# Adafruit_HX711_ADC_Breakout.net
KiCad netlist of a schematic drawn in EAGLE
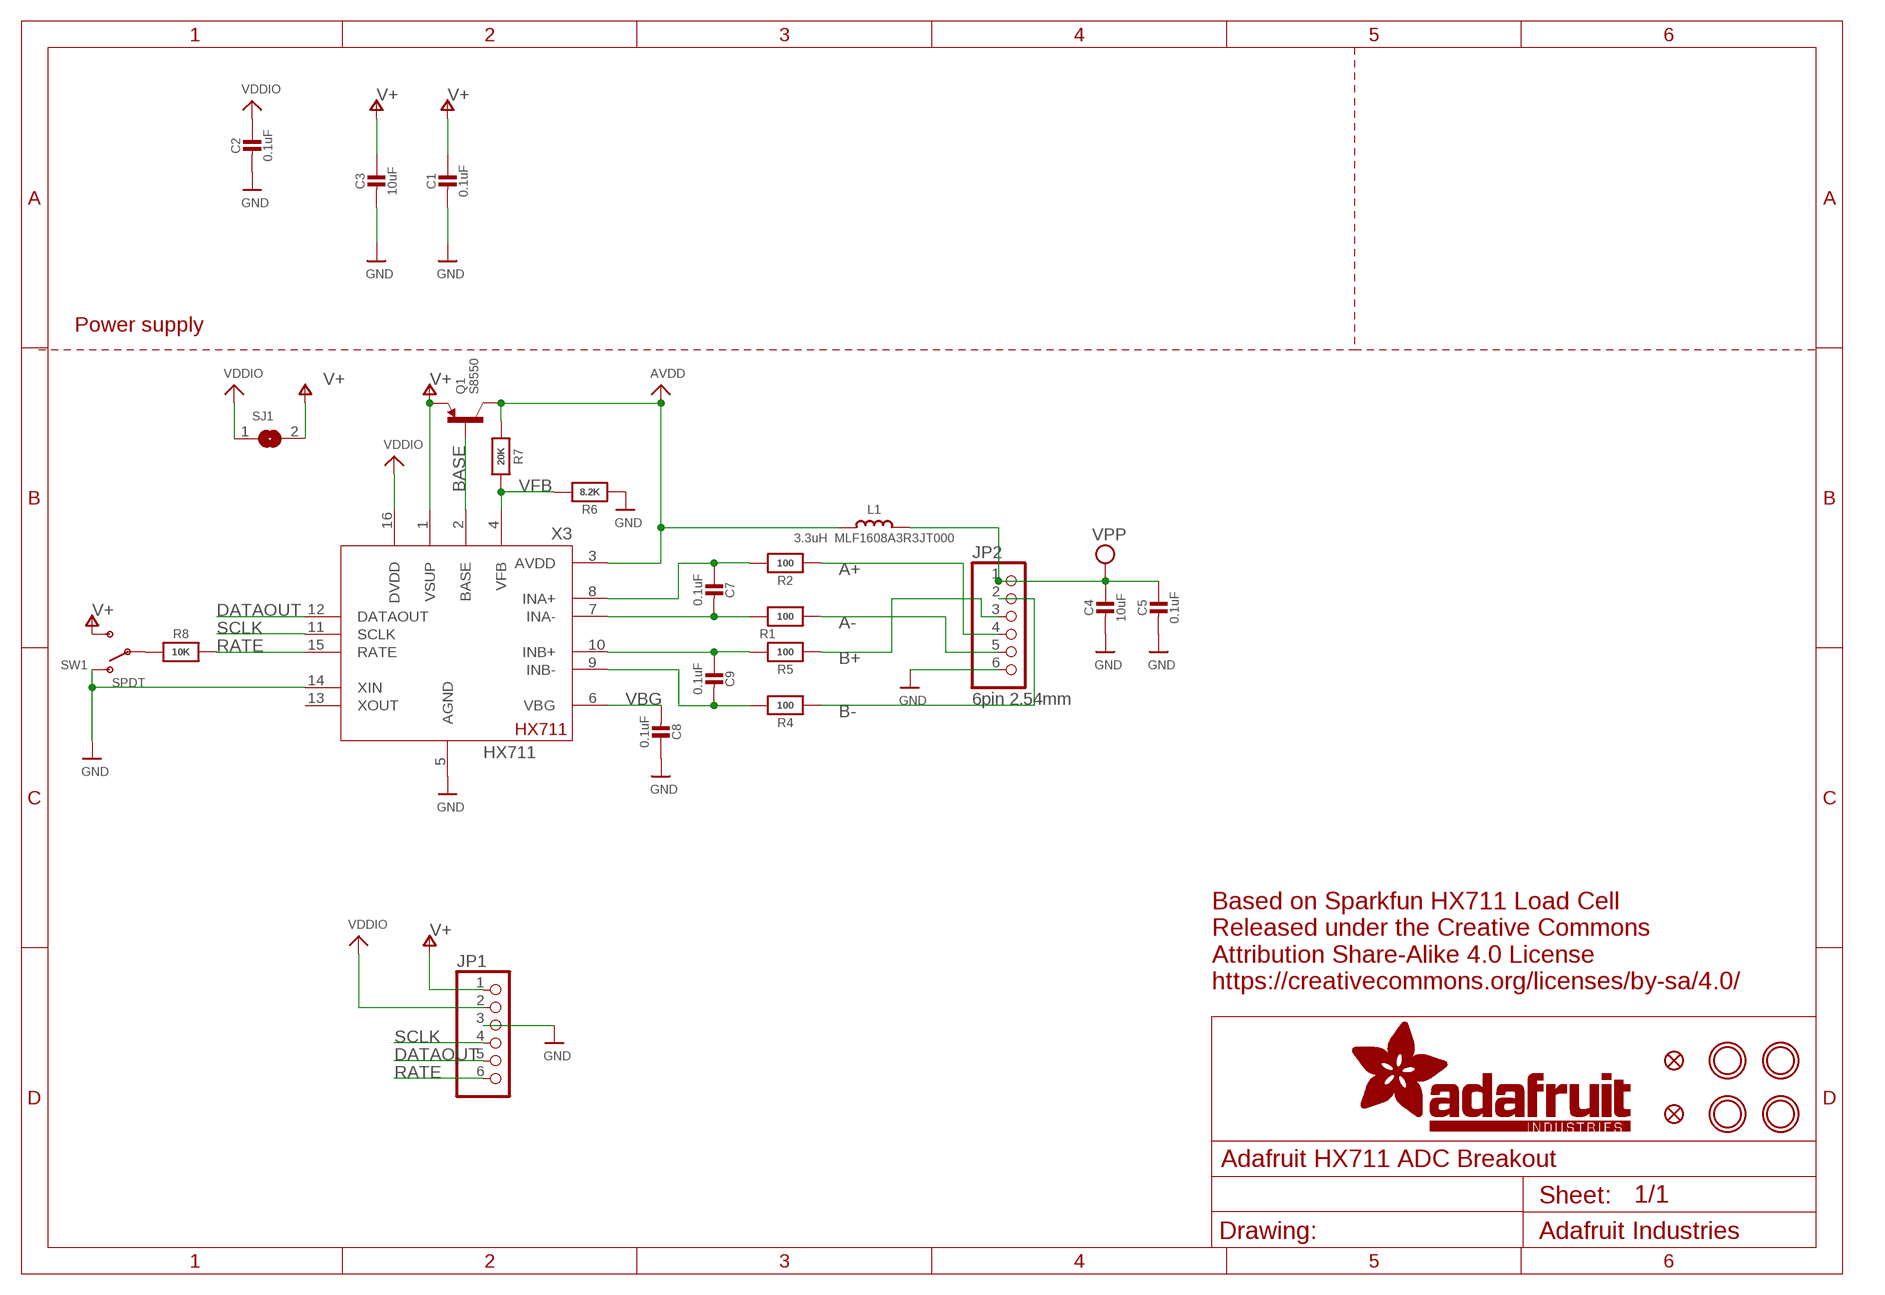
[diagram p0: schematic, sheet 1]

(export (version "E")
  (design (tool "Eeschema 10.0.6"))
  (components
    (comp (ref "C1")
      (value "0.1uF")
      (footprint "eagle-import:0603-NO")
      (libsource (lib "eagle-import") (part "CAP_CERAMIC0603_NO"))
    )
    (comp (ref "C2")
      (value "0.1uF")
      (footprint "eagle-import:0603-NO")
      (libsource (lib "eagle-import") (part "CAP_CERAMIC0603_NO"))
    )
    (comp (ref "C3")
      (value "10uF")
      (footprint "eagle-import:0805-NO")
      (libsource (lib "eagle-import") (part "CAP_CERAMIC0805-NOOUTLINE"))
    )
    (comp (ref "C4")
      (value "10uF")
      (footprint "eagle-import:0805-NO")
      (libsource (lib "eagle-import") (part "CAP_CERAMIC0805-NOOUTLINE"))
    )
    (comp (ref "C5")
      (value "0.1uF")
      (footprint "eagle-import:0603-NO")
      (libsource (lib "eagle-import") (part "CAP_CERAMIC0603_NO"))
    )
    (comp (ref "C7")
      (value "0.1uF")
      (footprint "eagle-import:0603-NO")
      (libsource (lib "eagle-import") (part "CAP_CERAMIC0603_NO"))
    )
    (comp (ref "C8")
      (value "0.1uF")
      (footprint "eagle-import:0603-NO")
      (libsource (lib "eagle-import") (part "CAP_CERAMIC0603_NO"))
    )
    (comp (ref "C9")
      (value "0.1uF")
      (footprint "eagle-import:0603-NO")
      (libsource (lib "eagle-import") (part "CAP_CERAMIC0603_NO"))
    )
    (comp (ref "FID3")
      (value "FIDUCIAL_0.5MM")
      (footprint "eagle-import:FIDUCIAL_0.5MM")
      (libsource (lib "eagle-import") (part "FIDUCIAL_0.5MM"))
    )
    (comp (ref "FID4")
      (value "FIDUCIAL_0.5MM")
      (footprint "eagle-import:FIDUCIAL_0.5MM")
      (libsource (lib "eagle-import") (part "FIDUCIAL_0.5MM"))
    )
    (comp (ref "JP1")
      (value "HEADER-1X670MIL")
      (footprint "eagle-import:1X06_ROUND_70")
      (libsource (lib "eagle-import") (part "HEADER-1X670MIL"))
    )
    (comp (ref "JP2")
      (value "6pin 2.54mm")
      (footprint "eagle-import:1X06_2.54MMTERMINAL")
      (libsource (lib "eagle-import") (part "HEADER-1X6_2.54MMTERM"))
    )
    (comp (ref "L1")
      (value "3.3uH MLF1608A3R3JT000")
      (footprint "eagle-import:0603-NO")
      (libsource (lib "eagle-import") (part "INDUCTOR0603_NO"))
    )
    (comp (ref "Q1")
      (value "S8550")
      (footprint "eagle-import:SOT23-WIDE")
      (libsource (lib "eagle-import") (part "TRANSISTOR_PNPWIDE"))
    )
    (comp (ref "R1")
      (value "100")
      (footprint "eagle-import:0603-NO")
      (libsource (lib "eagle-import") (part "RESISTOR_0603_NOOUT"))
    )
    (comp (ref "R2")
      (value "100")
      (footprint "eagle-import:0603-NO")
      (libsource (lib "eagle-import") (part "RESISTOR_0603_NOOUT"))
    )
    (comp (ref "R4")
      (value "100")
      (footprint "eagle-import:0603-NO")
      (libsource (lib "eagle-import") (part "RESISTOR_0603_NOOUT"))
    )
    (comp (ref "R5")
      (value "100")
      (footprint "eagle-import:0603-NO")
      (libsource (lib "eagle-import") (part "RESISTOR_0603_NOOUT"))
    )
    (comp (ref "R6")
      (value "8.2K")
      (footprint "eagle-import:0603-NO")
      (libsource (lib "eagle-import") (part "RESISTOR_0603_NOOUT"))
    )
    (comp (ref "R7")
      (value "20K")
      (footprint "eagle-import:0603-NO")
      (libsource (lib "eagle-import") (part "RESISTOR_0603_NOOUT"))
    )
    (comp (ref "R8")
      (value "10K")
      (footprint "eagle-import:0603-NO")
      (libsource (lib "eagle-import") (part "RESISTOR_0603_NOOUT"))
    )
    (comp (ref "SJ1")
      (value "SOLDERJUMPER")
      (footprint "eagle-import:SOLDERJUMPER_ARROW_NOPASTE")
      (libsource (lib "eagle-import") (part "SOLDERJUMPER"))
    )
    (comp (ref "SW1")
      (value "SPDT")
      (footprint "eagle-import:SPDT_SMT_SSSS811101")
      (libsource (lib "eagle-import") (part "SWITCH_SPDT"))
    )
    (comp (ref "U$1")
      (value "MOUNTINGHOLE2.5")
      (footprint "eagle-import:MOUNTINGHOLE_2.5_PLATED")
      (libsource (lib "eagle-import") (part "MOUNTINGHOLE2.5"))
    )
    (comp (ref "U$17")
      (value "MOUNTINGHOLE2.5")
      (footprint "eagle-import:MOUNTINGHOLE_2.5_PLATED")
      (libsource (lib "eagle-import") (part "MOUNTINGHOLE2.5"))
    )
    (comp (ref "U$19")
      (value "MOUNTINGHOLE2.5")
      (footprint "eagle-import:MOUNTINGHOLE_2.5_PLATED")
      (libsource (lib "eagle-import") (part "MOUNTINGHOLE2.5"))
    )
    (comp (ref "U$21")
      (value "MOUNTINGHOLE2.5")
      (footprint "eagle-import:MOUNTINGHOLE_2.5_PLATED")
      (libsource (lib "eagle-import") (part "MOUNTINGHOLE2.5"))
    )
    (comp (ref "X3")
      (value "HX711")
      (footprint "eagle-import:SO16")
      (libsource (lib "eagle-import") (part "HX711"))
    )
  )
  (nets
    (net (code "1") (name "/A+") (class "Default")
      (node (ref "JP2") (pin "4") (pinfunction "4_4") (pintype "passive"))
      (node (ref "R2") (pin "2") (pinfunction "2_2") (pintype "passive"))
    )
    (net (code "2") (name "/A-") (class "Default")
      (node (ref "JP2") (pin "5") (pinfunction "5_5") (pintype "passive"))
      (node (ref "R1") (pin "2") (pinfunction "2_2") (pintype "passive"))
    )
    (net (code "3") (name "/B+") (class "Default")
      (node (ref "JP2") (pin "3") (pinfunction "3_3") (pintype "passive"))
      (node (ref "R5") (pin "2") (pinfunction "2_2") (pintype "passive"))
    )
    (net (code "4") (name "/B-") (class "Default")
      (node (ref "JP2") (pin "2") (pinfunction "2_2") (pintype "passive"))
      (node (ref "R4") (pin "2") (pinfunction "2_2") (pintype "passive"))
    )
    (net (code "5") (name "/BASE") (class "Default")
      (node (ref "Q1") (pin "1") (pinfunction "B_1") (pintype "passive"))
      (node (ref "X3") (pin "2") (pinfunction "BASE_2") (pintype "power_in"))
    )
    (net (code "6") (name "/DATAOUT") (class "Default")
      (node (ref "JP1") (pin "5") (pinfunction "5_5") (pintype "passive"))
      (node (ref "X3") (pin "12") (pinfunction "DATAOUT_12") (pintype "output"))
    )
    (net (code "7") (name "/RATE") (class "Default")
      (node (ref "JP1") (pin "6") (pinfunction "6_6") (pintype "passive"))
      (node (ref "R8") (pin "1") (pinfunction "1_1") (pintype "passive"))
      (node (ref "X3") (pin "15") (pinfunction "RATE_15") (pintype "input"))
    )
    (net (code "8") (name "/SCLK") (class "Default")
      (node (ref "JP1") (pin "4") (pinfunction "4_4") (pintype "passive"))
      (node (ref "X3") (pin "11") (pinfunction "SCLK_11") (pintype "input"))
    )
    (net (code "9") (name "/VBG") (class "Default")
      (node (ref "C8") (pin "2") (pinfunction "2_2") (pintype "passive"))
      (node (ref "X3") (pin "6") (pinfunction "VBG_6") (pintype "power_in"))
    )
    (net (code "10") (name "/VFB") (class "Default")
      (node (ref "R6") (pin "1") (pinfunction "1_1") (pintype "passive"))
      (node (ref "R7") (pin "1") (pinfunction "1_1") (pintype "passive"))
      (node (ref "X3") (pin "4") (pinfunction "VFB_4") (pintype "power_in"))
    )
    (net (code "11") (name "AVDD") (class "Default")
      (node (ref "L1") (pin "1") (pinfunction "1_1") (pintype "passive"))
      (node (ref "Q1") (pin "3") (pinfunction "C_3") (pintype "passive"))
      (node (ref "R7") (pin "2") (pinfunction "2_2") (pintype "passive"))
      (node (ref "X3") (pin "3") (pinfunction "AVDD_3") (pintype "power_in"))
    )
    (net (code "12") (name "GND") (class "Default")
      (node (ref "C1") (pin "2") (pinfunction "2_2") (pintype "passive"))
      (node (ref "C2") (pin "2") (pinfunction "2_2") (pintype "passive"))
      (node (ref "C3") (pin "2") (pinfunction "2_2") (pintype "passive"))
      (node (ref "C4") (pin "2") (pinfunction "2_2") (pintype "passive"))
      (node (ref "C5") (pin "2") (pinfunction "2_2") (pintype "passive"))
      (node (ref "C8") (pin "1") (pinfunction "1_1") (pintype "passive"))
      (node (ref "JP1") (pin "3") (pinfunction "3_3") (pintype "passive"))
      (node (ref "JP2") (pin "6") (pinfunction "6_6") (pintype "passive"))
      (node (ref "R6") (pin "2") (pinfunction "2_2") (pintype "passive"))
      (node (ref "SW1") (pin "A") (pinfunction "O_A") (pintype "passive"))
      (node (ref "X3") (pin "14") (pinfunction "XIN_14") (pintype "passive"))
      (node (ref "X3") (pin "5") (pinfunction "AGND_5") (pintype "power_in"))
    )
    (net (code "13") (name "Net-(SW1-P)") (class "Default")
      (node (ref "R8") (pin "2") (pinfunction "2_2") (pintype "passive"))
      (node (ref "SW1") (pin "B") (pinfunction "P_B") (pintype "passive"))
    )
    (net (code "14") (name "Net-(X3-INA+)") (class "Default")
      (node (ref "C7") (pin "1") (pinfunction "1_1") (pintype "passive"))
      (node (ref "R2") (pin "1") (pinfunction "1_1") (pintype "passive"))
      (node (ref "X3") (pin "8") (pinfunction "INA+_8") (pintype "input"))
    )
    (net (code "15") (name "Net-(X3-INA-)") (class "Default")
      (node (ref "C7") (pin "2") (pinfunction "2_2") (pintype "passive"))
      (node (ref "R1") (pin "1") (pinfunction "1_1") (pintype "passive"))
      (node (ref "X3") (pin "7") (pinfunction "INA-_7") (pintype "input"))
    )
    (net (code "16") (name "Net-(X3-INB+)") (class "Default")
      (node (ref "C9") (pin "1") (pinfunction "1_1") (pintype "passive"))
      (node (ref "R5") (pin "1") (pinfunction "1_1") (pintype "passive"))
      (node (ref "X3") (pin "10") (pinfunction "INB+_10") (pintype "input"))
    )
    (net (code "17") (name "Net-(X3-INB-)") (class "Default")
      (node (ref "C9") (pin "2") (pinfunction "2_2") (pintype "passive"))
      (node (ref "R4") (pin "1") (pinfunction "1_1") (pintype "passive"))
      (node (ref "X3") (pin "9") (pinfunction "INB-_9") (pintype "input"))
    )
    (net (code "18") (name "V+") (class "Default")
      (node (ref "C1") (pin "1") (pinfunction "1_1") (pintype "passive"))
      (node (ref "C3") (pin "1") (pinfunction "1_1") (pintype "passive"))
      (node (ref "JP1") (pin "1") (pinfunction "1_1") (pintype "passive"))
      (node (ref "Q1") (pin "2") (pinfunction "E_2") (pintype "passive"))
      (node (ref "SJ1") (pin "2") (pinfunction "2_2") (pintype "passive"))
      (node (ref "SW1") (pin "C") (pinfunction "S_C") (pintype "passive"))
      (node (ref "X3") (pin "1") (pinfunction "VSUP_1") (pintype "power_in"))
    )
    (net (code "19") (name "VDDIO") (class "Default")
      (node (ref "C2") (pin "1") (pinfunction "1_1") (pintype "passive"))
      (node (ref "JP1") (pin "2") (pinfunction "2_2") (pintype "passive"))
      (node (ref "SJ1") (pin "1") (pinfunction "1_1") (pintype "passive"))
      (node (ref "X3") (pin "16") (pinfunction "DVDD_16") (pintype "power_in"))
    )
    (net (code "20") (name "VPP") (class "Default")
      (node (ref "C4") (pin "1") (pinfunction "1_1") (pintype "passive"))
      (node (ref "C5") (pin "1") (pinfunction "1_1") (pintype "passive"))
      (node (ref "JP2") (pin "1") (pinfunction "1_1") (pintype "passive"))
      (node (ref "L1") (pin "2") (pinfunction "2_2") (pintype "passive"))
    )
    (net (code "21") (name "unconnected-(X3-XOUT-Pad13)") (class "Default")
      (node (ref "X3") (pin "13") (pinfunction "XOUT_13") (pintype "passive"))
    )
  )
)
